# bias.net
KiCad netlist of a schematic drawn in EAGLE
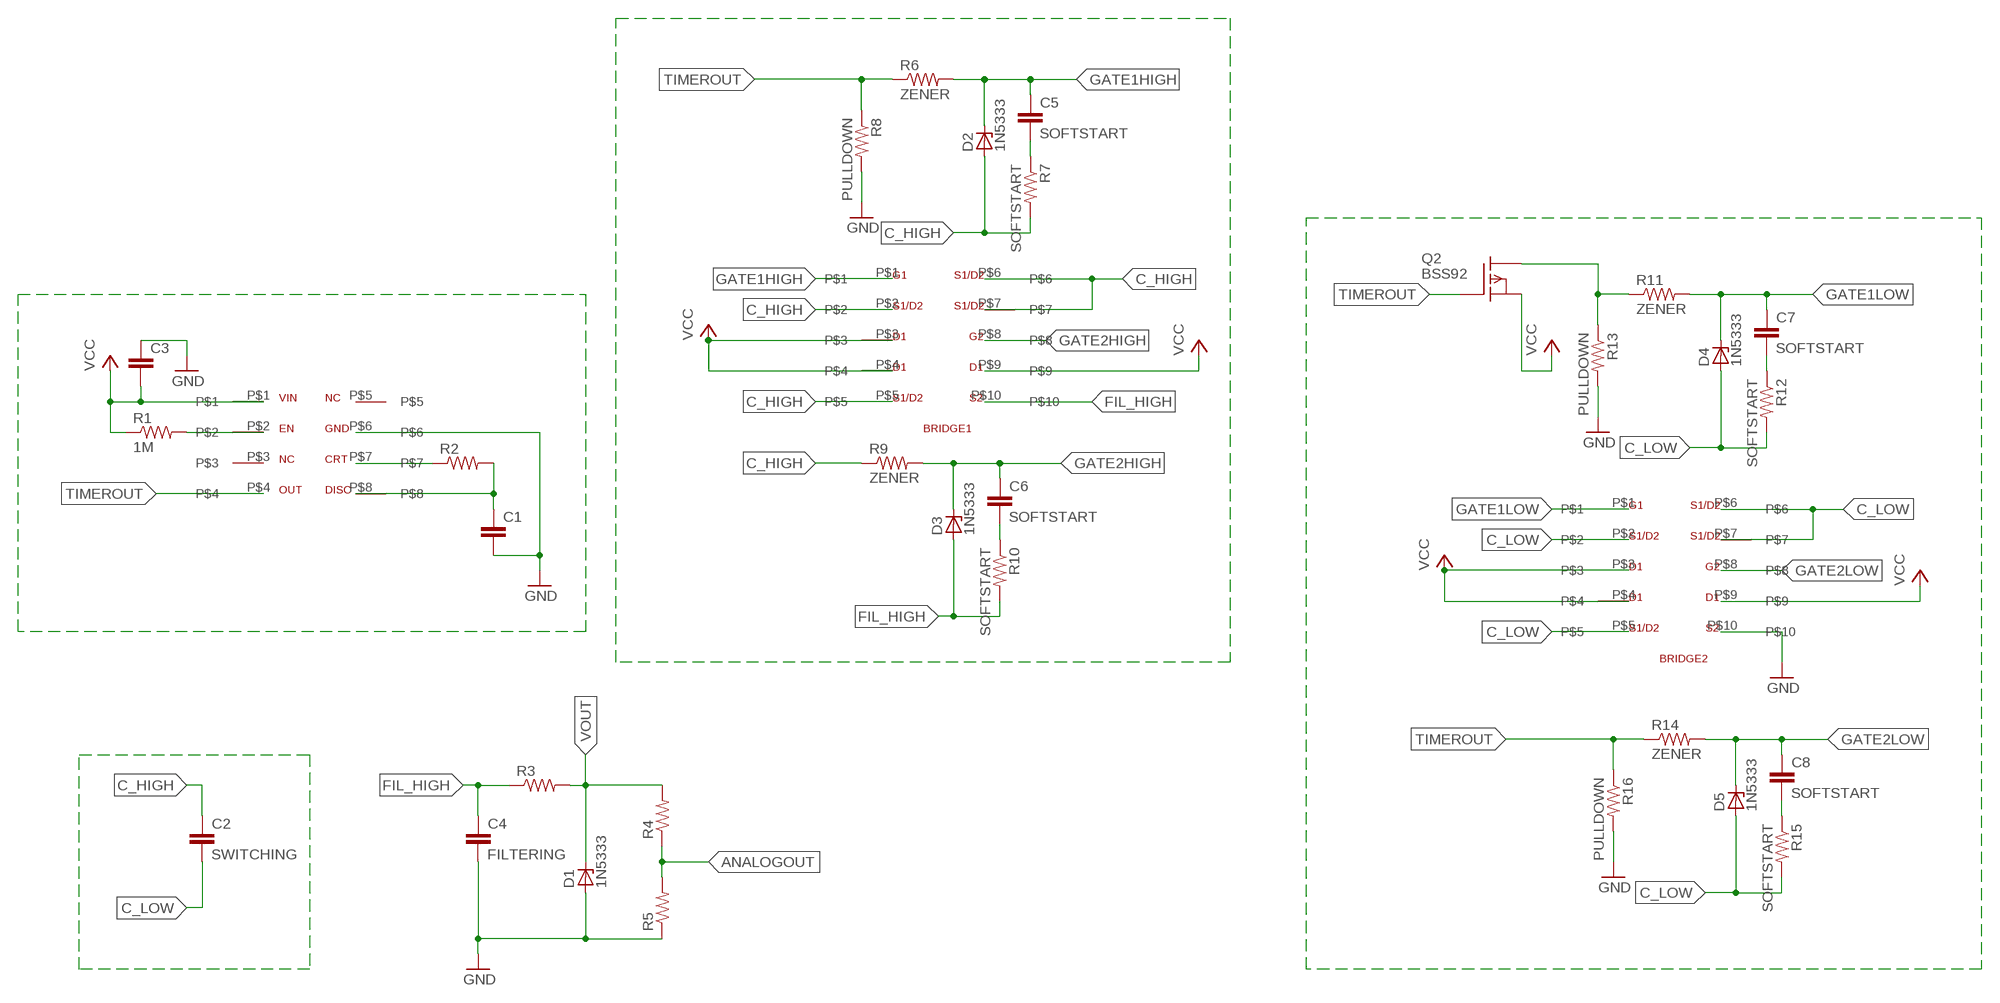
[diagram p0: schematic, sheet 1]

(export (version "E")
  (design (tool "Eeschema 10.0.6"))
  (components
    (comp (ref "BRIDGE1")
      (value "FDMD85100")
      (footprint "eagle-import:HALFBRIDGE")
      (libsource (lib "eagle-import") (part "FDMD85100"))
    )
    (comp (ref "BRIDGE2")
      (value "FDMD85100")
      (footprint "eagle-import:HALFBRIDGE")
      (libsource (lib "eagle-import") (part "FDMD85100"))
    )
    (comp (ref "C1")
      (value "CC1206")
      (footprint "eagle-import:C1206")
      (libsource (lib "eagle-import") (part "CC1206"))
    )
    (comp (ref "C2")
      (value "SWITCHING")
      (footprint "eagle-import:C1206")
      (libsource (lib "eagle-import") (part "CC1206"))
    )
    (comp (ref "C3")
      (value "CC1206")
      (footprint "eagle-import:C1206")
      (libsource (lib "eagle-import") (part "CC1206"))
    )
    (comp (ref "C4")
      (value "FILTERING")
      (footprint "eagle-import:C1206")
      (libsource (lib "eagle-import") (part "CC1206"))
    )
    (comp (ref "C5")
      (value "SOFTSTART")
      (footprint "eagle-import:C1206")
      (libsource (lib "eagle-import") (part "CC1206"))
    )
    (comp (ref "C6")
      (value "SOFTSTART")
      (footprint "eagle-import:C1206")
      (libsource (lib "eagle-import") (part "CC1206"))
    )
    (comp (ref "C7")
      (value "SOFTSTART")
      (footprint "eagle-import:C1206")
      (libsource (lib "eagle-import") (part "CC1206"))
    )
    (comp (ref "C8")
      (value "SOFTSTART")
      (footprint "eagle-import:C1206")
      (libsource (lib "eagle-import") (part "CC1206"))
    )
    (comp (ref "D1")
      (value "1N5333")
      (footprint "eagle-import:C1702-15")
      (libsource (lib "eagle-import") (part "1N5333"))
    )
    (comp (ref "D2")
      (value "1N5333")
      (footprint "eagle-import:C1702-15")
      (libsource (lib "eagle-import") (part "1N5333"))
    )
    (comp (ref "D3")
      (value "1N5333")
      (footprint "eagle-import:C1702-15")
      (libsource (lib "eagle-import") (part "1N5333"))
    )
    (comp (ref "D4")
      (value "1N5333")
      (footprint "eagle-import:C1702-15")
      (libsource (lib "eagle-import") (part "1N5333"))
    )
    (comp (ref "D5")
      (value "1N5333")
      (footprint "eagle-import:C1702-15")
      (libsource (lib "eagle-import") (part "1N5333"))
    )
    (comp (ref "Q2")
      (value "BSS92")
      (footprint "eagle-import:TO92")
      (libsource (lib "eagle-import") (part "BSS92"))
    )
    (comp (ref "R1")
      (value "1M")
      (footprint "eagle-import:R1210")
      (libsource (lib "eagle-import") (part "R-US_R1210"))
    )
    (comp (ref "R2")
      (value "R-US_R1210")
      (footprint "eagle-import:R1210")
      (libsource (lib "eagle-import") (part "R-US_R1210"))
    )
    (comp (ref "R3")
      (value "R-US_R1210")
      (footprint "eagle-import:R1210")
      (libsource (lib "eagle-import") (part "R-US_R1210"))
    )
    (comp (ref "R4")
      (value "R-US_R1210")
      (footprint "eagle-import:R1210")
      (libsource (lib "eagle-import") (part "R-US_R1210"))
    )
    (comp (ref "R5")
      (value "R-US_R1210")
      (footprint "eagle-import:R1210")
      (libsource (lib "eagle-import") (part "R-US_R1210"))
    )
    (comp (ref "R6")
      (value "ZENER")
      (footprint "eagle-import:R1210")
      (libsource (lib "eagle-import") (part "R-US_R1210"))
    )
    (comp (ref "R7")
      (value "SOFTSTART")
      (footprint "eagle-import:R1210")
      (libsource (lib "eagle-import") (part "R-US_R1210"))
    )
    (comp (ref "R8")
      (value "PULLDOWN")
      (footprint "eagle-import:R1210")
      (libsource (lib "eagle-import") (part "R-US_R1210"))
    )
    (comp (ref "R9")
      (value "ZENER")
      (footprint "eagle-import:R1210")
      (libsource (lib "eagle-import") (part "R-US_R1210"))
    )
    (comp (ref "R10")
      (value "SOFTSTART")
      (footprint "eagle-import:R1210")
      (libsource (lib "eagle-import") (part "R-US_R1210"))
    )
    (comp (ref "R11")
      (value "ZENER")
      (footprint "eagle-import:R1210")
      (libsource (lib "eagle-import") (part "R-US_R1210"))
    )
    (comp (ref "R12")
      (value "SOFTSTART")
      (footprint "eagle-import:R1210")
      (libsource (lib "eagle-import") (part "R-US_R1210"))
    )
    (comp (ref "R13")
      (value "PULLDOWN")
      (footprint "eagle-import:R1210")
      (libsource (lib "eagle-import") (part "R-US_R1210"))
    )
    (comp (ref "R14")
      (value "ZENER")
      (footprint "eagle-import:R1210")
      (libsource (lib "eagle-import") (part "R-US_R1210"))
    )
    (comp (ref "R15")
      (value "SOFTSTART")
      (footprint "eagle-import:R1210")
      (libsource (lib "eagle-import") (part "R-US_R1210"))
    )
    (comp (ref "R16")
      (value "PULLDOWN")
      (footprint "eagle-import:R1210")
      (libsource (lib "eagle-import") (part "R-US_R1210"))
    )
    (comp (ref "U$1")
      (value "BD9555FVM-C")
      (footprint "eagle-import:MSOP8")
      (libsource (lib "eagle-import") (part "BD9555FVM-C"))
    )
  )
  (nets
    (net (code "1") (name "ANALOGOUT") (class "Default")
      (node (ref "R4") (pin "1") (pinfunction "1_1") (pintype "passive"))
      (node (ref "R5") (pin "2") (pinfunction "2_2") (pintype "passive"))
    )
    (net (code "2") (name "C_HIGH") (class "Default")
      (node (ref "BRIDGE1") (pin "P$2") (pinfunction "P$2_P$2") (pintype "bidirectional"))
      (node (ref "BRIDGE1") (pin "P$5") (pinfunction "P$5_P$5") (pintype "bidirectional"))
      (node (ref "BRIDGE1") (pin "P$6") (pinfunction "P$6_P$6") (pintype "bidirectional"))
      (node (ref "BRIDGE1") (pin "P$7") (pinfunction "P$7_P$7") (pintype "bidirectional"))
      (node (ref "C2") (pin "1") (pinfunction "1_1") (pintype "passive"))
      (node (ref "D2") (pin "A") (pinfunction "A_A") (pintype "passive"))
      (node (ref "R7") (pin "2") (pinfunction "2_2") (pintype "passive"))
      (node (ref "R9") (pin "1") (pinfunction "1_1") (pintype "passive"))
    )
    (net (code "3") (name "C_LOW") (class "Default")
      (node (ref "BRIDGE2") (pin "P$2") (pinfunction "P$2_P$2") (pintype "bidirectional"))
      (node (ref "BRIDGE2") (pin "P$5") (pinfunction "P$5_P$5") (pintype "bidirectional"))
      (node (ref "BRIDGE2") (pin "P$6") (pinfunction "P$6_P$6") (pintype "bidirectional"))
      (node (ref "BRIDGE2") (pin "P$7") (pinfunction "P$7_P$7") (pintype "bidirectional"))
      (node (ref "C2") (pin "2") (pinfunction "2_2") (pintype "passive"))
      (node (ref "D4") (pin "A") (pinfunction "A_A") (pintype "passive"))
      (node (ref "D5") (pin "A") (pinfunction "A_A") (pintype "passive"))
      (node (ref "R12") (pin "2") (pinfunction "2_2") (pintype "passive"))
      (node (ref "R15") (pin "2") (pinfunction "2_2") (pintype "passive"))
    )
    (net (code "4") (name "FIL_HIGH") (class "Default")
      (node (ref "BRIDGE1") (pin "P$10") (pinfunction "P$10_P$10") (pintype "bidirectional"))
      (node (ref "C4") (pin "1") (pinfunction "1_1") (pintype "passive"))
      (node (ref "D3") (pin "A") (pinfunction "A_A") (pintype "passive"))
      (node (ref "R10") (pin "2") (pinfunction "2_2") (pintype "passive"))
      (node (ref "R3") (pin "1") (pinfunction "1_1") (pintype "passive"))
    )
    (net (code "5") (name "GATE1HIGH") (class "Default")
      (node (ref "BRIDGE1") (pin "P$1") (pinfunction "P$1_P$1") (pintype "bidirectional"))
      (node (ref "C5") (pin "1") (pinfunction "1_1") (pintype "passive"))
      (node (ref "D2") (pin "C") (pinfunction "C_C") (pintype "passive"))
      (node (ref "R6") (pin "2") (pinfunction "2_2") (pintype "passive"))
    )
    (net (code "6") (name "GATE1LOW") (class "Default")
      (node (ref "BRIDGE2") (pin "P$1") (pinfunction "P$1_P$1") (pintype "bidirectional"))
      (node (ref "C7") (pin "1") (pinfunction "1_1") (pintype "passive"))
      (node (ref "D4") (pin "C") (pinfunction "C_C") (pintype "passive"))
      (node (ref "R11") (pin "2") (pinfunction "2_2") (pintype "passive"))
    )
    (net (code "7") (name "GATE2HIGH") (class "Default")
      (node (ref "BRIDGE1") (pin "P$8") (pinfunction "P$8_P$8") (pintype "bidirectional"))
      (node (ref "C6") (pin "1") (pinfunction "1_1") (pintype "passive"))
      (node (ref "D3") (pin "C") (pinfunction "C_C") (pintype "passive"))
      (node (ref "R9") (pin "2") (pinfunction "2_2") (pintype "passive"))
    )
    (net (code "8") (name "GATE2LOW") (class "Default")
      (node (ref "BRIDGE2") (pin "P$8") (pinfunction "P$8_P$8") (pintype "bidirectional"))
      (node (ref "C8") (pin "1") (pinfunction "1_1") (pintype "passive"))
      (node (ref "D5") (pin "C") (pinfunction "C_C") (pintype "passive"))
      (node (ref "R14") (pin "2") (pinfunction "2_2") (pintype "passive"))
    )
    (net (code "9") (name "GND") (class "Default")
      (node (ref "BRIDGE2") (pin "P$10") (pinfunction "P$10_P$10") (pintype "bidirectional"))
      (node (ref "C1") (pin "2") (pinfunction "2_2") (pintype "passive"))
      (node (ref "C3") (pin "1") (pinfunction "1_1") (pintype "passive"))
      (node (ref "C4") (pin "2") (pinfunction "2_2") (pintype "passive"))
      (node (ref "D1") (pin "A") (pinfunction "A_A") (pintype "passive"))
      (node (ref "R13") (pin "2") (pinfunction "2_2") (pintype "passive"))
      (node (ref "R16") (pin "2") (pinfunction "2_2") (pintype "passive"))
      (node (ref "R5") (pin "1") (pinfunction "1_1") (pintype "passive"))
      (node (ref "R8") (pin "2") (pinfunction "2_2") (pintype "passive"))
      (node (ref "U$1") (pin "P$6") (pinfunction "P$6_P$6") (pintype "bidirectional"))
    )
    (net (code "10") (name "Net-(C1-Pad1)") (class "Default")
      (node (ref "C1") (pin "1") (pinfunction "1_1") (pintype "passive"))
      (node (ref "R2") (pin "2") (pinfunction "2_2") (pintype "passive"))
      (node (ref "U$1") (pin "P$8") (pinfunction "P$8_P$8") (pintype "bidirectional"))
    )
    (net (code "11") (name "Net-(C5-Pad2)") (class "Default")
      (node (ref "C5") (pin "2") (pinfunction "2_2") (pintype "passive"))
      (node (ref "R7") (pin "1") (pinfunction "1_1") (pintype "passive"))
    )
    (net (code "12") (name "Net-(C6-Pad2)") (class "Default")
      (node (ref "C6") (pin "2") (pinfunction "2_2") (pintype "passive"))
      (node (ref "R10") (pin "1") (pinfunction "1_1") (pintype "passive"))
    )
    (net (code "13") (name "Net-(C7-Pad2)") (class "Default")
      (node (ref "C7") (pin "2") (pinfunction "2_2") (pintype "passive"))
      (node (ref "R12") (pin "1") (pinfunction "1_1") (pintype "passive"))
    )
    (net (code "14") (name "Net-(C8-Pad2)") (class "Default")
      (node (ref "C8") (pin "2") (pinfunction "2_2") (pintype "passive"))
      (node (ref "R15") (pin "1") (pinfunction "1_1") (pintype "passive"))
    )
    (net (code "15") (name "Net-(R1-Pad2)") (class "Default")
      (node (ref "R1") (pin "2") (pinfunction "2_2") (pintype "passive"))
      (node (ref "U$1") (pin "P$2") (pinfunction "P$2_P$2") (pintype "bidirectional"))
    )
    (net (code "16") (name "Net-(R2-Pad1)") (class "Default")
      (node (ref "R2") (pin "1") (pinfunction "1_1") (pintype "passive"))
      (node (ref "U$1") (pin "P$7") (pinfunction "P$7_P$7") (pintype "bidirectional"))
    )
    (net (code "17") (name "TIMEROUT") (class "Default")
      (node (ref "Q2") (pin "2") (pinfunction "D_2") (pintype "passive"))
      (node (ref "R11") (pin "1") (pinfunction "1_1") (pintype "passive"))
      (node (ref "R13") (pin "1") (pinfunction "1_1") (pintype "passive"))
      (node (ref "R14") (pin "1") (pinfunction "1_1") (pintype "passive"))
      (node (ref "R16") (pin "1") (pinfunction "1_1") (pintype "passive"))
      (node (ref "R6") (pin "1") (pinfunction "1_1") (pintype "passive"))
      (node (ref "R8") (pin "1") (pinfunction "1_1") (pintype "passive"))
      (node (ref "U$1") (pin "P$4") (pinfunction "P$4_P$4") (pintype "bidirectional"))
    )
    (net (code "18") (name "VCC") (class "Default")
      (node (ref "BRIDGE1") (pin "P$3") (pinfunction "P$3_P$3") (pintype "bidirectional"))
      (node (ref "BRIDGE1") (pin "P$4") (pinfunction "P$4_P$4") (pintype "bidirectional"))
      (node (ref "BRIDGE1") (pin "P$9") (pinfunction "P$9_P$9") (pintype "bidirectional"))
      (node (ref "BRIDGE2") (pin "P$3") (pinfunction "P$3_P$3") (pintype "bidirectional"))
      (node (ref "BRIDGE2") (pin "P$4") (pinfunction "P$4_P$4") (pintype "bidirectional"))
      (node (ref "BRIDGE2") (pin "P$9") (pinfunction "P$9_P$9") (pintype "bidirectional"))
      (node (ref "C3") (pin "2") (pinfunction "2_2") (pintype "passive"))
      (node (ref "Q2") (pin "3") (pinfunction "S_3") (pintype "passive"))
      (node (ref "R1") (pin "1") (pinfunction "1_1") (pintype "passive"))
      (node (ref "U$1") (pin "P$1") (pinfunction "P$1_P$1") (pintype "bidirectional"))
    )
    (net (code "19") (name "VOUT") (class "Default")
      (node (ref "D1") (pin "C") (pinfunction "C_C") (pintype "passive"))
      (node (ref "R3") (pin "2") (pinfunction "2_2") (pintype "passive"))
      (node (ref "R4") (pin "2") (pinfunction "2_2") (pintype "passive"))
    )
    (net (code "20") (name "unconnected-(Q2-G-Pad1)") (class "Default")
      (node (ref "Q2") (pin "1") (pinfunction "G_1") (pintype "passive"))
    )
    (net (code "21") (name "unconnected-(U$1-PadP$3)") (class "Default")
      (node (ref "U$1") (pin "P$3") (pinfunction "P$3_P$3") (pintype "bidirectional"))
    )
    (net (code "22") (name "unconnected-(U$1-PadP$5)") (class "Default")
      (node (ref "U$1") (pin "P$5") (pinfunction "P$5_P$5") (pintype "bidirectional"))
    )
  )
)
